# kwatch-v1-rev1.net
KiCad netlist of a schematic drawn in EAGLE
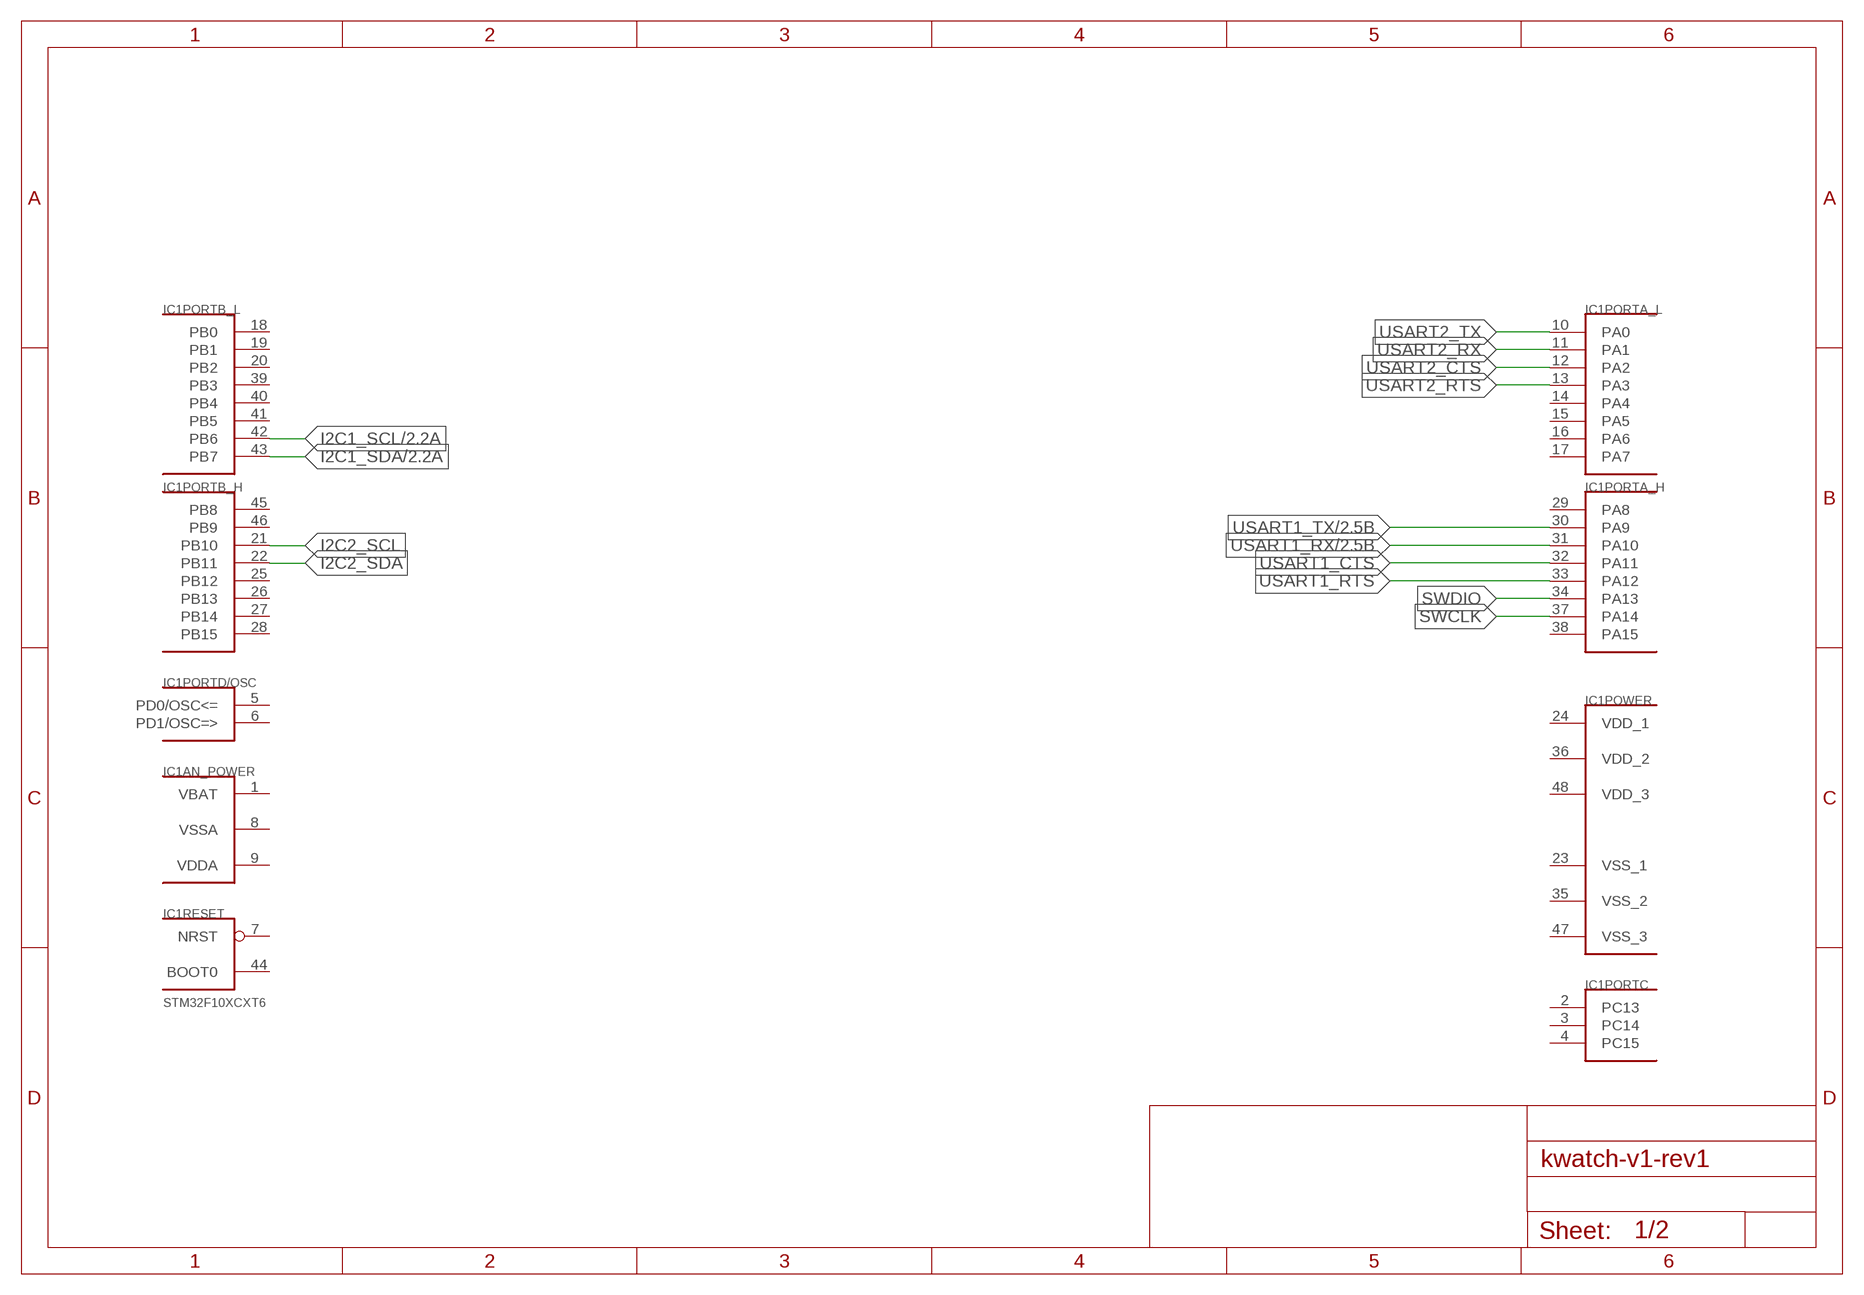
[diagram p0: schematic, sheet 1]
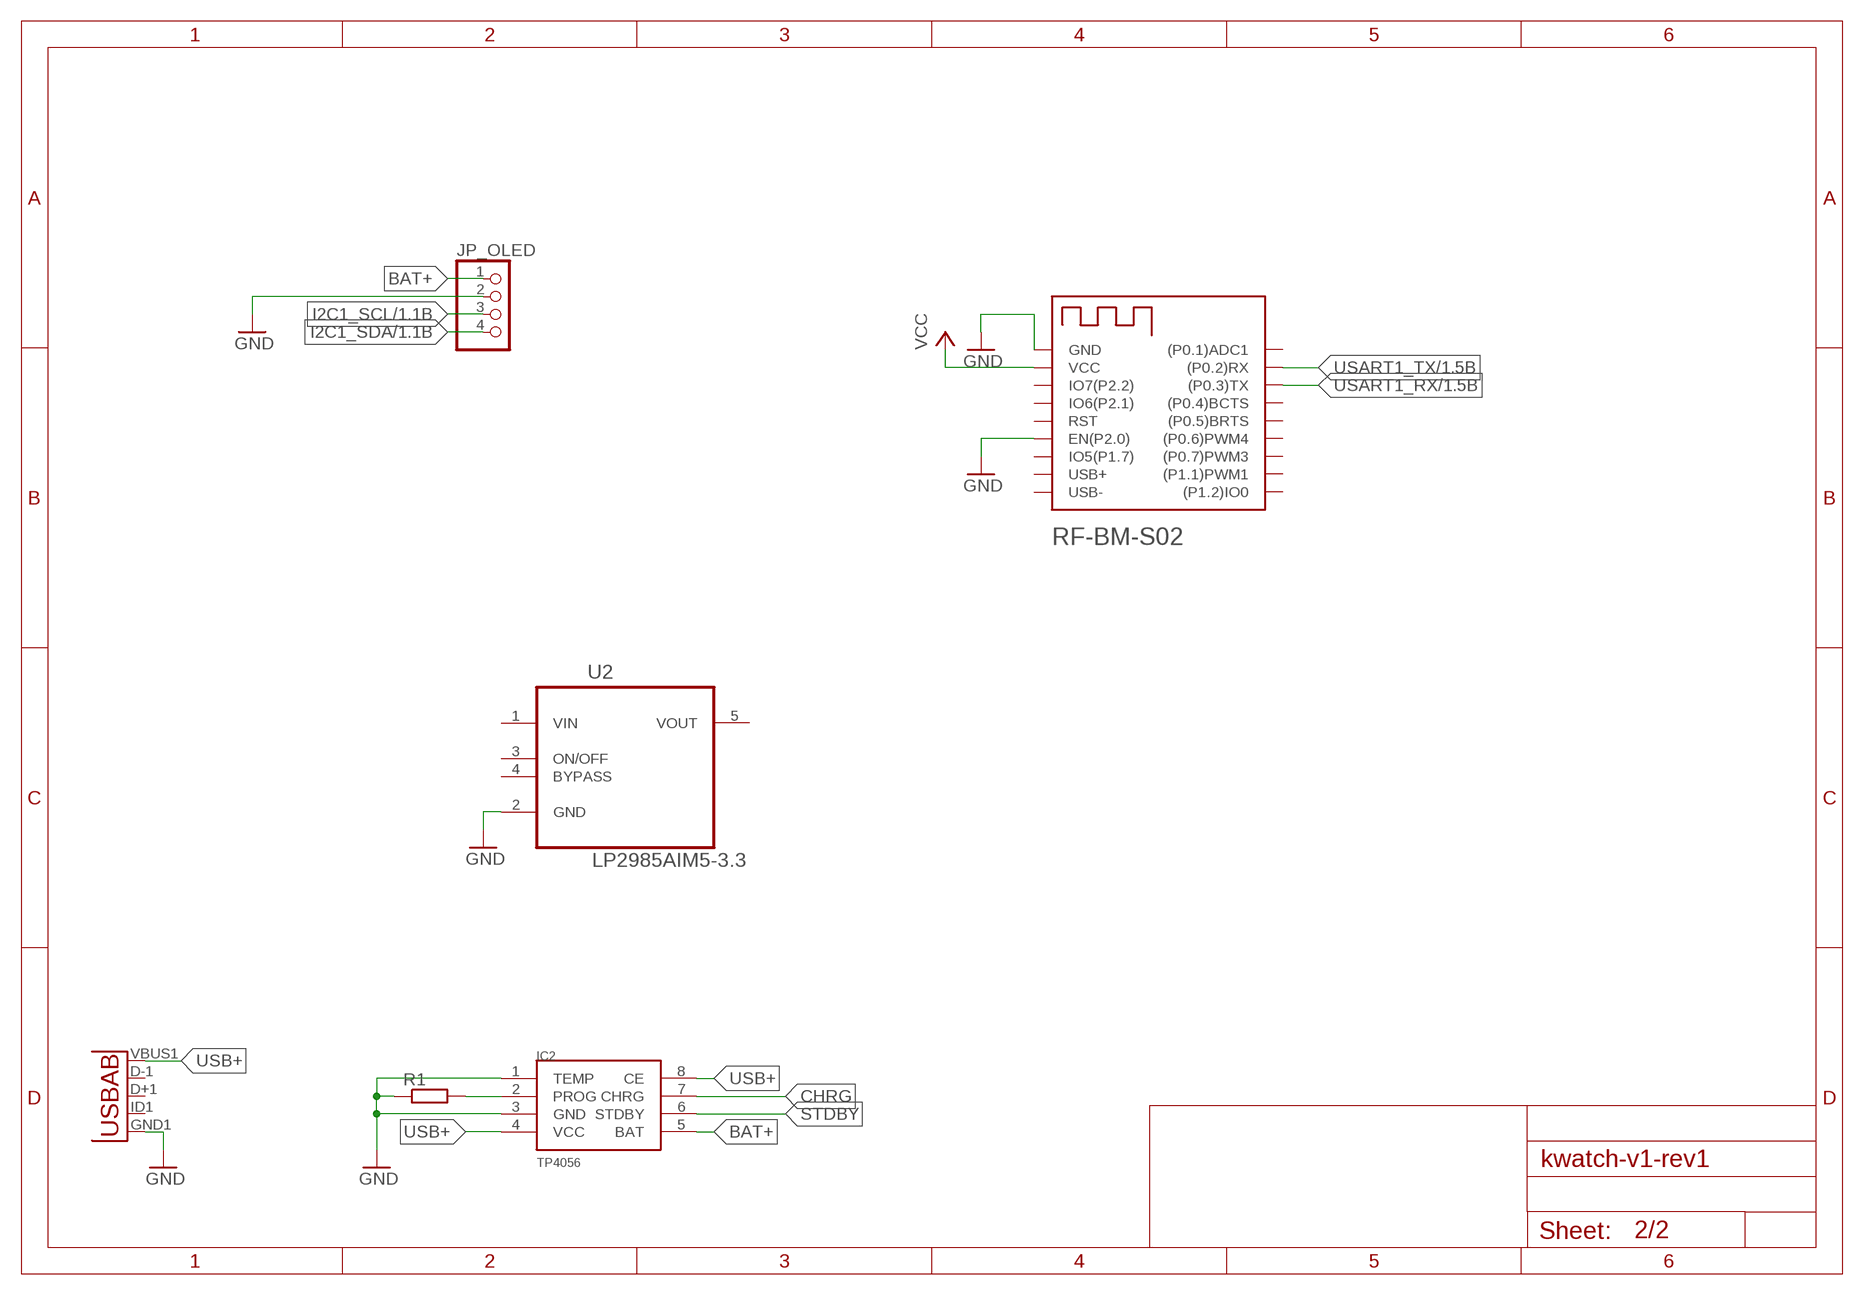
[diagram p1: schematic, sheet 2]

(export (version "E")
  (design (tool "Eeschema 10.0.6"))
  (components
    (comp (ref "BM-S1")
      (value "RF-BM-S02")
      (footprint "eagle-import:RF-BM-S02")
      (libsource (lib "eagle-import") (part "RF-BM-S02"))
    )
    (comp (ref "IC2")
      (value "TP4056")
      (footprint "eagle-import:SOP-8")
      (libsource (lib "eagle-import") (part "TP4056"))
    )
    (comp (ref "JP_OLED")
      (value "PINHD-1X04_2.00")
      (footprint "eagle-import:1X04M")
      (libsource (lib "eagle-import") (part "PINHD-1X04_2.00"))
    )
    (comp (ref "R1")
      (value "R-EU_R0805")
      (footprint "eagle-import:R0805")
      (libsource (lib "eagle-import") (part "R-EU_R0805"))
    )
    (comp (ref "U1")
      (value "USB\"\"")
      (footprint "eagle-import:USB-MICRO-SMD")
      (libsource (lib "eagle-import") (part "USB{dblquote}{dblquote}"))
    )
    (comp (ref "U2")
      (value "LP2985AIM5-3.3")
      (footprint "eagle-import:SOT95P284X119-5N")
      (libsource (lib "eagle-import") (part "LP2985AIM5-3.3"))
    )
    (comp (ref "IC1")
      (value "STM32F10XCXT6")
      (footprint "eagle-import:TQFP48")
      (libsource (lib "eagle-import") (part "STM32F10XCXT6"))
    )
  )
  (nets
    (net (code "1") (name "BAT+") (class "Default")
      (node (ref "IC2") (pin "5") (pinfunction "BAT_5") (pintype "bidirectional"))
      (node (ref "JP_OLED") (pin "1") (pinfunction "1_1") (pintype "passive"))
    )
    (net (code "2") (name "CHRG") (class "Default")
      (node (ref "IC2") (pin "7") (pinfunction "CHRG_7") (pintype "bidirectional"))
    )
    (net (code "3") (name "GND") (class "Default")
      (node (ref "BM-S1") (pin "P$1") (pinfunction "GND_P$1") (pintype "power_in"))
      (node (ref "BM-S1") (pin "P$6") (pinfunction "EN(P2.0)_P$6") (pintype "input"))
      (node (ref "IC2") (pin "1") (pinfunction "TEMP_1") (pintype "bidirectional"))
      (node (ref "IC2") (pin "3") (pinfunction "GND_3") (pintype "bidirectional"))
      (node (ref "JP_OLED") (pin "2") (pinfunction "2_2") (pintype "passive"))
      (node (ref "R1") (pin "1") (pinfunction "1_1") (pintype "passive"))
      (node (ref "U1") (pin "GND1") (pinfunction "GND_GND1") (pintype "bidirectional"))
      (node (ref "U2") (pin "2") (pinfunction "GND_2") (pintype "passive"))
    )
    (net (code "4") (name "I2C1_SCL") (class "Default")
      (node (ref "IC1") (pin "42") (pinfunction "PB6_42") (pintype "bidirectional"))
      (node (ref "JP_OLED") (pin "3") (pinfunction "3_3") (pintype "passive"))
    )
    (net (code "5") (name "I2C1_SDA") (class "Default")
      (node (ref "IC1") (pin "43") (pinfunction "PB7_43") (pintype "bidirectional"))
      (node (ref "JP_OLED") (pin "4") (pinfunction "4_4") (pintype "passive"))
    )
    (net (code "6") (name "I2C2_SCL") (class "Default")
      (node (ref "IC1") (pin "21") (pinfunction "PB10_21") (pintype "bidirectional"))
    )
    (net (code "7") (name "I2C2_SDA") (class "Default")
      (node (ref "IC1") (pin "22") (pinfunction "PB11_22") (pintype "bidirectional"))
    )
    (net (code "8") (name "Net-(IC2-PROG)") (class "Default")
      (node (ref "IC2") (pin "2") (pinfunction "PROG_2") (pintype "bidirectional"))
      (node (ref "R1") (pin "2") (pinfunction "2_2") (pintype "passive"))
    )
    (net (code "9") (name "STDBY") (class "Default")
      (node (ref "IC2") (pin "6") (pinfunction "STDBY_6") (pintype "bidirectional"))
    )
    (net (code "10") (name "SWCLK") (class "Default")
      (node (ref "IC1") (pin "37") (pinfunction "PA14_37") (pintype "bidirectional"))
    )
    (net (code "11") (name "SWDIO") (class "Default")
      (node (ref "IC1") (pin "34") (pinfunction "PA13_34") (pintype "bidirectional"))
    )
    (net (code "12") (name "USART1_CTS") (class "Default")
      (node (ref "IC1") (pin "32") (pinfunction "PA11_32") (pintype "bidirectional"))
    )
    (net (code "13") (name "USART1_RTS") (class "Default")
      (node (ref "IC1") (pin "33") (pinfunction "PA12_33") (pintype "bidirectional"))
    )
    (net (code "14") (name "USART1_RX") (class "Default")
      (node (ref "BM-S1") (pin "P$16") (pinfunction "(P0.3)TX_P$16") (pintype "output"))
      (node (ref "IC1") (pin "31") (pinfunction "PA10_31") (pintype "bidirectional"))
    )
    (net (code "15") (name "USART1_TX") (class "Default")
      (node (ref "BM-S1") (pin "P$17") (pinfunction "(P0.2)RX_P$17") (pintype "input"))
      (node (ref "IC1") (pin "30") (pinfunction "PA9_30") (pintype "bidirectional"))
    )
    (net (code "16") (name "USART2_CTS") (class "Default")
      (node (ref "IC1") (pin "12") (pinfunction "PA2_12") (pintype "bidirectional"))
    )
    (net (code "17") (name "USART2_RTS") (class "Default")
      (node (ref "IC1") (pin "13") (pinfunction "PA3_13") (pintype "bidirectional"))
    )
    (net (code "18") (name "USART2_RX") (class "Default")
      (node (ref "IC1") (pin "11") (pinfunction "PA1_11") (pintype "bidirectional"))
    )
    (net (code "19") (name "USART2_TX") (class "Default")
      (node (ref "IC1") (pin "10") (pinfunction "PA0_10") (pintype "bidirectional"))
    )
    (net (code "20") (name "USB+") (class "Default")
      (node (ref "IC2") (pin "4") (pinfunction "VCC_4") (pintype "bidirectional"))
      (node (ref "IC2") (pin "8") (pinfunction "CE_8") (pintype "bidirectional"))
      (node (ref "U1") (pin "VBUS1") (pinfunction "VBUS_VBUS1") (pintype "bidirectional"))
    )
    (net (code "21") (name "VCC") (class "Default")
      (node (ref "BM-S1") (pin "P$2") (pinfunction "VCC_P$2") (pintype "power_in"))
    )
    (net (code "22") (name "VDD_1") (class "Default")
      (node (ref "IC1") (pin "24") (pinfunction "VDD_1_24") (pintype "power_in"))
    )
    (net (code "23") (name "VDD_2") (class "Default")
      (node (ref "IC1") (pin "36") (pinfunction "VDD_2_36") (pintype "power_in"))
    )
    (net (code "24") (name "VDD_3") (class "Default")
      (node (ref "IC1") (pin "48") (pinfunction "VDD_3_48") (pintype "power_in"))
    )
    (net (code "25") (name "VIN") (class "Default")
      (node (ref "U2") (pin "1") (pinfunction "VIN_1") (pintype "power_in"))
    )
    (net (code "26") (name "VSS_1") (class "Default")
      (node (ref "IC1") (pin "23") (pinfunction "VSS_1_23") (pintype "power_in"))
    )
    (net (code "27") (name "VSS_2") (class "Default")
      (node (ref "IC1") (pin "35") (pinfunction "VSS_2_35") (pintype "power_in"))
    )
    (net (code "28") (name "VSS_3") (class "Default")
      (node (ref "IC1") (pin "47") (pinfunction "VSS_3_47") (pintype "power_in"))
    )
    (net (code "29") (name "unconnected-(BM-S1-(P0.1)ADC1-PadP$18)") (class "Default")
      (node (ref "BM-S1") (pin "P$18") (pinfunction "(P0.1)ADC1_P$18") (pintype "input"))
    )
    (net (code "30") (name "unconnected-(BM-S1-(P0.4)BCTS-PadP$15)") (class "Default")
      (node (ref "BM-S1") (pin "P$15") (pinfunction "(P0.4)BCTS_P$15") (pintype "output"))
    )
    (net (code "31") (name "unconnected-(BM-S1-(P0.5)BRTS-PadP$14)") (class "Default")
      (node (ref "BM-S1") (pin "P$14") (pinfunction "(P0.5)BRTS_P$14") (pintype "bidirectional"))
    )
    (net (code "32") (name "unconnected-(BM-S1-(P0.6)PWM4-PadP$13)") (class "Default")
      (node (ref "BM-S1") (pin "P$13") (pinfunction "(P0.6)PWM4_P$13") (pintype "output"))
    )
    (net (code "33") (name "unconnected-(BM-S1-(P0.7)PWM3-PadP$12)") (class "Default")
      (node (ref "BM-S1") (pin "P$12") (pinfunction "(P0.7)PWM3_P$12") (pintype "output"))
    )
    (net (code "34") (name "unconnected-(BM-S1-(P1.1)PWM1-PadP$11)") (class "Default")
      (node (ref "BM-S1") (pin "P$11") (pinfunction "(P1.1)PWM1_P$11") (pintype "output"))
    )
    (net (code "35") (name "unconnected-(BM-S1-(P1.2)IO0-PadP$10)") (class "Default")
      (node (ref "BM-S1") (pin "P$10") (pinfunction "(P1.2)IO0_P$10") (pintype "bidirectional"))
    )
    (net (code "36") (name "unconnected-(BM-S1-IO5(P1.7)-PadP$7)") (class "Default")
      (node (ref "BM-S1") (pin "P$7") (pinfunction "IO5(P1.7)_P$7") (pintype "bidirectional"))
    )
    (net (code "37") (name "unconnected-(BM-S1-IO6(P2.1)-PadP$4)") (class "Default")
      (node (ref "BM-S1") (pin "P$4") (pinfunction "IO6(P2.1)_P$4") (pintype "output"))
    )
    (net (code "38") (name "unconnected-(BM-S1-IO7(P2.2)-PadP$3)") (class "Default")
      (node (ref "BM-S1") (pin "P$3") (pinfunction "IO7(P2.2)_P$3") (pintype "output"))
    )
    (net (code "39") (name "unconnected-(BM-S1-RST-PadP$5)") (class "Default")
      (node (ref "BM-S1") (pin "P$5") (pinfunction "RST_P$5") (pintype "input"))
    )
    (net (code "40") (name "unconnected-(BM-S1-USB+-PadP$8)") (class "Default")
      (node (ref "BM-S1") (pin "P$8") (pinfunction "USB+_P$8") (pintype "bidirectional"))
    )
    (net (code "41") (name "unconnected-(BM-S1-USB--PadP$9)") (class "Default")
      (node (ref "BM-S1") (pin "P$9") (pinfunction "USB-_P$9") (pintype "bidirectional"))
    )
    (net (code "42") (name "unconnected-(IC1A-VBAT-Pad1)") (class "Default")
      (node (ref "IC1") (pin "1") (pinfunction "VBAT_1") (pintype "power_in"))
    )
    (net (code "43") (name "unconnected-(IC1A-VDDA-Pad9)") (class "Default")
      (node (ref "IC1") (pin "9") (pinfunction "VDDA_9") (pintype "power_in"))
    )
    (net (code "44") (name "unconnected-(IC1A-VSSA-Pad8)") (class "Default")
      (node (ref "IC1") (pin "8") (pinfunction "VSSA_8") (pintype "power_in"))
    )
    (net (code "45") (name "unconnected-(IC1B-PA8-Pad29)") (class "Default")
      (node (ref "IC1") (pin "29") (pinfunction "PA8_29") (pintype "bidirectional"))
    )
    (net (code "46") (name "unconnected-(IC1B-PA15-Pad38)") (class "Default")
      (node (ref "IC1") (pin "38") (pinfunction "PA15_38") (pintype "bidirectional"))
    )
    (net (code "47") (name "unconnected-(IC1C-PA4-Pad14)") (class "Default")
      (node (ref "IC1") (pin "14") (pinfunction "PA4_14") (pintype "bidirectional"))
    )
    (net (code "48") (name "unconnected-(IC1C-PA5-Pad15)") (class "Default")
      (node (ref "IC1") (pin "15") (pinfunction "PA5_15") (pintype "bidirectional"))
    )
    (net (code "49") (name "unconnected-(IC1C-PA6-Pad16)") (class "Default")
      (node (ref "IC1") (pin "16") (pinfunction "PA6_16") (pintype "bidirectional"))
    )
    (net (code "50") (name "unconnected-(IC1C-PA7-Pad17)") (class "Default")
      (node (ref "IC1") (pin "17") (pinfunction "PA7_17") (pintype "bidirectional"))
    )
    (net (code "51") (name "unconnected-(IC1D-PB8-Pad45)") (class "Default")
      (node (ref "IC1") (pin "45") (pinfunction "PB8_45") (pintype "bidirectional"))
    )
    (net (code "52") (name "unconnected-(IC1D-PB9-Pad46)") (class "Default")
      (node (ref "IC1") (pin "46") (pinfunction "PB9_46") (pintype "bidirectional"))
    )
    (net (code "53") (name "unconnected-(IC1D-PB12-Pad25)") (class "Default")
      (node (ref "IC1") (pin "25") (pinfunction "PB12_25") (pintype "bidirectional"))
    )
    (net (code "54") (name "unconnected-(IC1D-PB13-Pad26)") (class "Default")
      (node (ref "IC1") (pin "26") (pinfunction "PB13_26") (pintype "bidirectional"))
    )
    (net (code "55") (name "unconnected-(IC1D-PB14-Pad27)") (class "Default")
      (node (ref "IC1") (pin "27") (pinfunction "PB14_27") (pintype "bidirectional"))
    )
    (net (code "56") (name "unconnected-(IC1D-PB15-Pad28)") (class "Default")
      (node (ref "IC1") (pin "28") (pinfunction "PB15_28") (pintype "bidirectional"))
    )
    (net (code "57") (name "unconnected-(IC1E-PB0-Pad18)") (class "Default")
      (node (ref "IC1") (pin "18") (pinfunction "PB0_18") (pintype "bidirectional"))
    )
    (net (code "58") (name "unconnected-(IC1E-PB1-Pad19)") (class "Default")
      (node (ref "IC1") (pin "19") (pinfunction "PB1_19") (pintype "bidirectional"))
    )
    (net (code "59") (name "unconnected-(IC1E-PB2-Pad20)") (class "Default")
      (node (ref "IC1") (pin "20") (pinfunction "PB2_20") (pintype "bidirectional"))
    )
    (net (code "60") (name "unconnected-(IC1E-PB3-Pad39)") (class "Default")
      (node (ref "IC1") (pin "39") (pinfunction "PB3_39") (pintype "bidirectional"))
    )
    (net (code "61") (name "unconnected-(IC1E-PB4-Pad40)") (class "Default")
      (node (ref "IC1") (pin "40") (pinfunction "PB4_40") (pintype "bidirectional"))
    )
    (net (code "62") (name "unconnected-(IC1E-PB5-Pad41)") (class "Default")
      (node (ref "IC1") (pin "41") (pinfunction "PB5_41") (pintype "bidirectional"))
    )
    (net (code "63") (name "unconnected-(IC1F-PC13-Pad2)") (class "Default")
      (node (ref "IC1") (pin "2") (pinfunction "PC13_2") (pintype "bidirectional"))
    )
    (net (code "64") (name "unconnected-(IC1F-PC14-Pad3)") (class "Default")
      (node (ref "IC1") (pin "3") (pinfunction "PC14_3") (pintype "bidirectional"))
    )
    (net (code "65") (name "unconnected-(IC1F-PC15-Pad4)") (class "Default")
      (node (ref "IC1") (pin "4") (pinfunction "PC15_4") (pintype "bidirectional"))
    )
    (net (code "66") (name "unconnected-(IC1G-PD0{slash}OSC<=-Pad5)") (class "Default")
      (node (ref "IC1") (pin "5") (pinfunction "PD0/OSC<=_5") (pintype "bidirectional"))
    )
    (net (code "67") (name "unconnected-(IC1G-PD1{slash}OSC=>-Pad6)") (class "Default")
      (node (ref "IC1") (pin "6") (pinfunction "PD1/OSC=>_6") (pintype "bidirectional"))
    )
    (net (code "68") (name "unconnected-(IC1I-BOOT0-Pad44)") (class "Default")
      (node (ref "IC1") (pin "44") (pinfunction "BOOT0_44") (pintype "input"))
    )
    (net (code "69") (name "unconnected-(IC1I-NRST-Pad7)") (class "Default")
      (node (ref "IC1") (pin "7") (pinfunction "NRST_7") (pintype "input"))
    )
    (net (code "70") (name "unconnected-(U1-D+-PadD+1)") (class "Default")
      (node (ref "U1") (pin "D+1") (pinfunction "D+_D+1") (pintype "bidirectional"))
    )
    (net (code "71") (name "unconnected-(U1-D--PadD-1)") (class "Default")
      (node (ref "U1") (pin "D-1") (pinfunction "D-_D-1") (pintype "bidirectional"))
    )
    (net (code "72") (name "unconnected-(U1-USBID-PadID1)") (class "Default")
      (node (ref "U1") (pin "ID1") (pinfunction "USBID_ID1") (pintype "bidirectional"))
    )
    (net (code "73") (name "unconnected-(U2-BYPASS-Pad4)") (class "Default")
      (node (ref "U2") (pin "4") (pinfunction "BYPASS_4") (pintype "passive"))
    )
    (net (code "74") (name "unconnected-(U2-ON{slash}OFF-Pad3)") (class "Default")
      (node (ref "U2") (pin "3") (pinfunction "ON/OFF_3") (pintype "input"))
    )
    (net (code "75") (name "unconnected-(U2-VOUT-Pad5)") (class "Default")
      (node (ref "U2") (pin "5") (pinfunction "VOUT_5") (pintype "output"))
    )
  )
)
